# SPT3G_AdapterBoard.net
KiCad netlist of a schematic drawn in Altium Designer
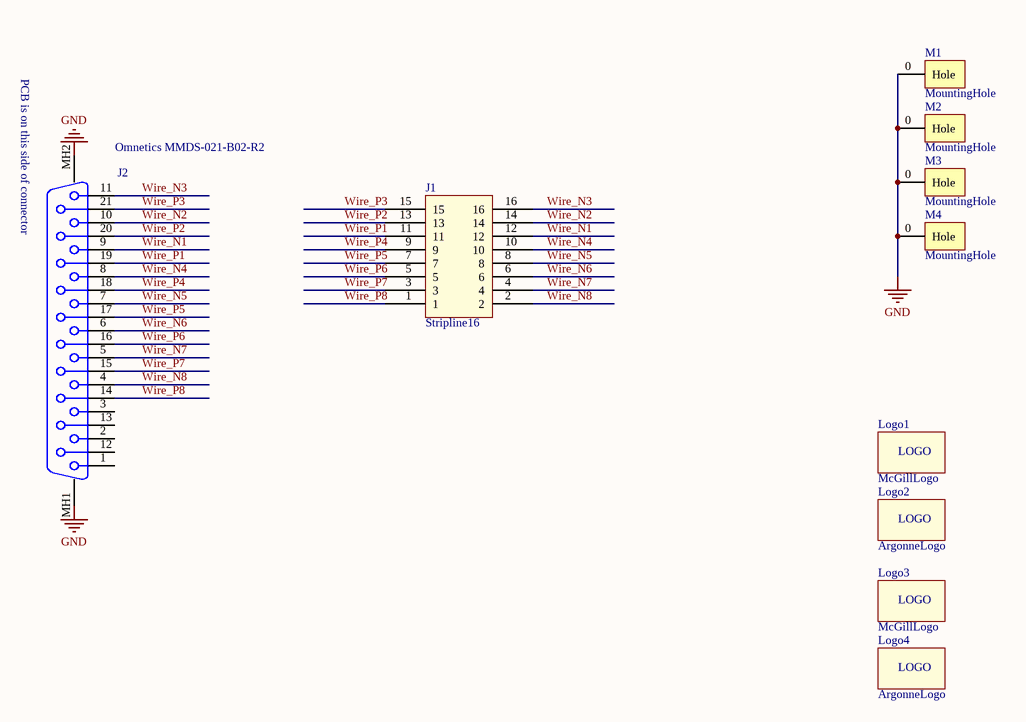
[diagram p0: SPT3G_AdapterBoard.SchDoc]

(export (version "E")
  (design (tool "Eeschema 10.0.6"))
  (components
    (comp (ref "J1")
      (value "Stripline16")
      (footprint "Stripline16-HalfLength")
      (description "Stripline16 2mm x 15mm pads")
      (libsource (lib "SPT3G_AdapterBoard") (part "Stripline16"))
    )
    (comp (ref "J2")
      (value "Omnetics MMDS-021-B02-R2")
      (footprint "MMDS-021-B02-R2")
      (description "OmneticsMicroD21")
      (libsource (lib "SPT3G_LCBoard") (part "OmneticsMicroD21"))
    )
    (comp (ref "Logo1")
      (value "McGillLogo")
      (footprint "McGillLogo1")
      (libsource (lib "SPT3G_AdapterBoard") (part "Logo"))
    )
    (comp (ref "Logo2")
      (value "ArgonneLogo")
      (footprint "ArgonneLogo")
      (libsource (lib "SPT3G_AdapterBoard") (part "Logo"))
    )
    (comp (ref "Logo3")
      (value "McGillLogo")
      (footprint "McGillLogo1")
      (libsource (lib "SPT3G_AdapterBoard") (part "Logo"))
    )
    (comp (ref "Logo4")
      (value "ArgonneLogo")
      (footprint "ArgonneLogo")
      (libsource (lib "SPT3G_AdapterBoard") (part "Logo"))
    )
    (comp (ref "M1")
      (value "MountingHole")
      (footprint "MountingHole")
      (libsource (lib "SPT3G_AdapterBoard") (part "MountingHole"))
    )
    (comp (ref "M2")
      (value "MountingHole")
      (footprint "MountingHole")
      (libsource (lib "SPT3G_AdapterBoard") (part "MountingHole"))
    )
    (comp (ref "M3")
      (value "MountingHole")
      (footprint "MountingHole")
      (libsource (lib "SPT3G_AdapterBoard") (part "MountingHole"))
    )
    (comp (ref "M4")
      (value "MountingHole")
      (footprint "MountingHole")
      (libsource (lib "SPT3G_AdapterBoard") (part "MountingHole"))
    )
  )
  (nets
    (net (code "1") (name "/Wire_N1") (class "Default")
      (node (ref "J1") (pin "12") (pinfunction "12_12") (pintype "passive"))
      (node (ref "J2") (pin "9") (pinfunction "9_9") (pintype "passive"))
    )
    (net (code "2") (name "/Wire_N2") (class "Default")
      (node (ref "J1") (pin "14") (pinfunction "14_14") (pintype "passive"))
      (node (ref "J2") (pin "10") (pinfunction "10_10") (pintype "passive"))
    )
    (net (code "3") (name "/Wire_N3") (class "Default")
      (node (ref "J1") (pin "16") (pinfunction "16_16") (pintype "passive"))
      (node (ref "J2") (pin "11") (pinfunction "11_11") (pintype "passive"))
    )
    (net (code "4") (name "/Wire_N4") (class "Default")
      (node (ref "J1") (pin "10") (pinfunction "10_10") (pintype "passive"))
      (node (ref "J2") (pin "8") (pinfunction "8_8") (pintype "passive"))
    )
    (net (code "5") (name "/Wire_N5") (class "Default")
      (node (ref "J1") (pin "8") (pinfunction "8_8") (pintype "passive"))
      (node (ref "J2") (pin "7") (pinfunction "7_7") (pintype "passive"))
    )
    (net (code "6") (name "/Wire_N6") (class "Default")
      (node (ref "J1") (pin "6") (pinfunction "6_6") (pintype "passive"))
      (node (ref "J2") (pin "6") (pinfunction "6_6") (pintype "passive"))
    )
    (net (code "7") (name "/Wire_N7") (class "Default")
      (node (ref "J1") (pin "4") (pinfunction "4_4") (pintype "passive"))
      (node (ref "J2") (pin "5") (pinfunction "5_5") (pintype "passive"))
    )
    (net (code "8") (name "/Wire_N8") (class "Default")
      (node (ref "J1") (pin "2") (pinfunction "2_2") (pintype "passive"))
      (node (ref "J2") (pin "4") (pinfunction "4_4") (pintype "passive"))
    )
    (net (code "9") (name "/Wire_P1") (class "Default")
      (node (ref "J1") (pin "11") (pinfunction "11_11") (pintype "passive"))
      (node (ref "J2") (pin "19") (pinfunction "19_19") (pintype "passive"))
    )
    (net (code "10") (name "/Wire_P2") (class "Default")
      (node (ref "J1") (pin "13") (pinfunction "13_13") (pintype "passive"))
      (node (ref "J2") (pin "20") (pinfunction "20_20") (pintype "passive"))
    )
    (net (code "11") (name "/Wire_P3") (class "Default")
      (node (ref "J1") (pin "15") (pinfunction "15_15") (pintype "passive"))
      (node (ref "J2") (pin "21") (pinfunction "21_21") (pintype "passive"))
    )
    (net (code "12") (name "/Wire_P4") (class "Default")
      (node (ref "J1") (pin "9") (pinfunction "9_9") (pintype "passive"))
      (node (ref "J2") (pin "18") (pinfunction "18_18") (pintype "passive"))
    )
    (net (code "13") (name "/Wire_P5") (class "Default")
      (node (ref "J1") (pin "7") (pinfunction "7_7") (pintype "passive"))
      (node (ref "J2") (pin "17") (pinfunction "17_17") (pintype "passive"))
    )
    (net (code "14") (name "/Wire_P6") (class "Default")
      (node (ref "J1") (pin "5") (pinfunction "5_5") (pintype "passive"))
      (node (ref "J2") (pin "16") (pinfunction "16_16") (pintype "passive"))
    )
    (net (code "15") (name "/Wire_P7") (class "Default")
      (node (ref "J1") (pin "3") (pinfunction "3_3") (pintype "passive"))
      (node (ref "J2") (pin "15") (pinfunction "15_15") (pintype "passive"))
    )
    (net (code "16") (name "/Wire_P8") (class "Default")
      (node (ref "J1") (pin "1") (pinfunction "1_1") (pintype "passive"))
      (node (ref "J2") (pin "14") (pinfunction "14_14") (pintype "passive"))
    )
    (net (code "17") (name "GND") (class "Default")
      (node (ref "J2") (pin "MH1") (pinfunction "MH1_MH1") (pintype "passive"))
      (node (ref "J2") (pin "MH2") (pinfunction "MH2_MH2") (pintype "passive"))
      (node (ref "M1") (pin "0") (pinfunction "Hole_0") (pintype "passive"))
      (node (ref "M2") (pin "0") (pinfunction "Hole_0") (pintype "passive"))
      (node (ref "M3") (pin "0") (pinfunction "Hole_0") (pintype "passive"))
      (node (ref "M4") (pin "0") (pinfunction "Hole_0") (pintype "passive"))
    )
    (net (code "18") (name "unconnected-(J2-Pad1)") (class "Default")
      (node (ref "J2") (pin "1") (pinfunction "1_1") (pintype "passive"))
    )
    (net (code "19") (name "unconnected-(J2-Pad2)") (class "Default")
      (node (ref "J2") (pin "2") (pinfunction "2_2") (pintype "passive"))
    )
    (net (code "20") (name "unconnected-(J2-Pad3)") (class "Default")
      (node (ref "J2") (pin "3") (pinfunction "3_3") (pintype "passive"))
    )
    (net (code "21") (name "unconnected-(J2-Pad12)") (class "Default")
      (node (ref "J2") (pin "12") (pinfunction "12_12") (pintype "passive"))
    )
    (net (code "22") (name "unconnected-(J2-Pad13)") (class "Default")
      (node (ref "J2") (pin "13") (pinfunction "13_13") (pintype "passive"))
    )
  )
)
